# ZXSC380FHTA.net
KiCad netlist of a schematic drawn in EAGLE
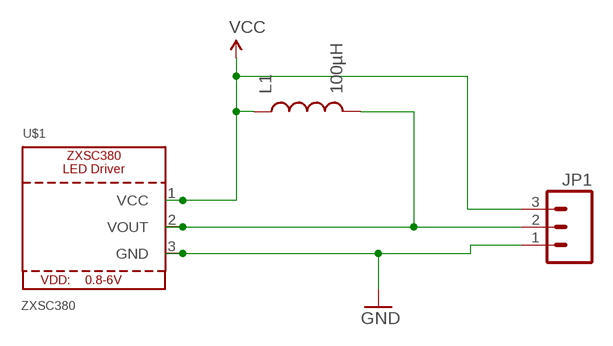
[diagram p0: schematic, sheet 1]

(export (version "E")
  (design (tool "Eeschema 10.0.6"))
  (components
    (comp (ref "JP1")
      (value "M03PTH")
      (footprint "eagle-import:1X03")
      (libsource (lib "eagle-import") (part "M03PTH"))
    )
    (comp (ref "L1")
      (value "100µH")
      (footprint "eagle-import:0805")
      (libsource (lib "eagle-import") (part "INDUCTOR0805"))
    )
    (comp (ref "U$1")
      (value "ZXSC380")
      (footprint "eagle-import:SOT-23")
      (libsource (lib "eagle-import") (part "ZXSC380"))
    )
  )
  (nets
    (net (code "1") (name "GND") (class "Default")
      (node (ref "JP1") (pin "1") (pinfunction "1_1") (pintype "passive"))
      (node (ref "U$1") (pin "3") (pinfunction "GND_3") (pintype "power_in"))
    )
    (net (code "2") (name "Net-(U$1-VOUT)") (class "Default")
      (node (ref "JP1") (pin "2") (pinfunction "2_2") (pintype "passive"))
      (node (ref "L1") (pin "2") (pinfunction "2_2") (pintype "passive"))
      (node (ref "U$1") (pin "2") (pinfunction "VOUT_2") (pintype "output"))
    )
    (net (code "3") (name "VCC") (class "Default")
      (node (ref "JP1") (pin "3") (pinfunction "3_3") (pintype "passive"))
      (node (ref "L1") (pin "1") (pinfunction "1_1") (pintype "passive"))
      (node (ref "U$1") (pin "1") (pinfunction "VCC_1") (pintype "power_in"))
    )
  )
)
